# main.net
KiCad netlist of a schematic drawn in EAGLE
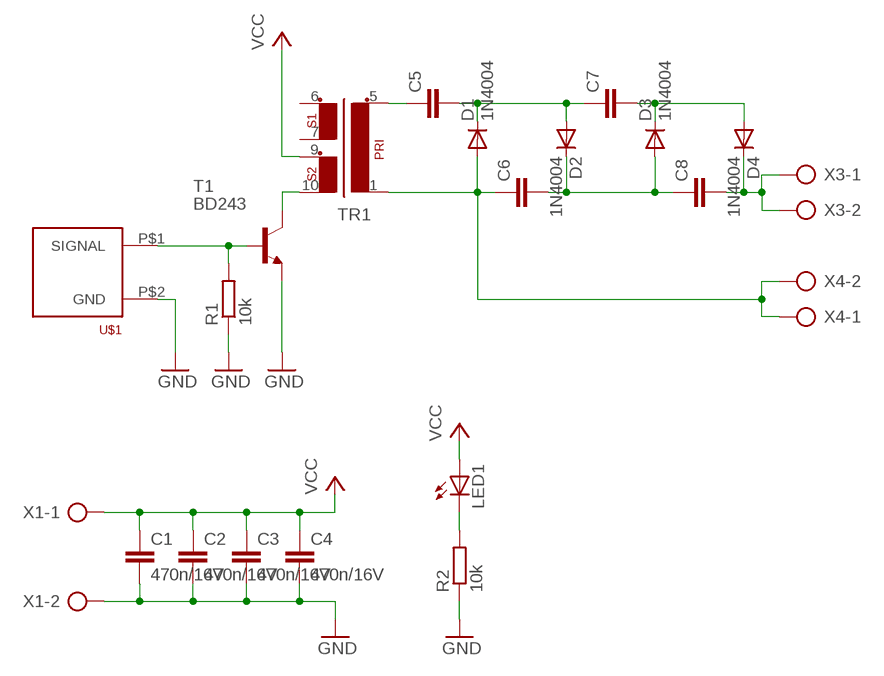
[diagram p0: schematic, sheet 1]

(export (version "E")
  (design (tool "Eeschema 10.0.6"))
  (components
    (comp (ref "C1")
      (value "470n/16V")
      (footprint "eagle-import:C025-025X050")
      (libsource (lib "eagle-import") (part "C-EU025-025X050"))
    )
    (comp (ref "C2")
      (value "470n/16V")
      (footprint "eagle-import:C025-025X050")
      (libsource (lib "eagle-import") (part "C-EU025-025X050"))
    )
    (comp (ref "C3")
      (value "470n/16V")
      (footprint "eagle-import:C025-025X050")
      (libsource (lib "eagle-import") (part "C-EU025-025X050"))
    )
    (comp (ref "C4")
      (value "470n/16V")
      (footprint "eagle-import:C025-025X050")
      (libsource (lib "eagle-import") (part "C-EU025-025X050"))
    )
    (comp (ref "C5")
      (value "C-EU150-064X183")
      (footprint "eagle-import:C150-064X183")
      (libsource (lib "eagle-import") (part "C-EU150-064X183"))
    )
    (comp (ref "C6")
      (value "C-EU150-064X183")
      (footprint "eagle-import:C150-064X183")
      (libsource (lib "eagle-import") (part "C-EU150-064X183"))
    )
    (comp (ref "C7")
      (value "C-EU150-064X183")
      (footprint "eagle-import:C150-064X183")
      (libsource (lib "eagle-import") (part "C-EU150-064X183"))
    )
    (comp (ref "C8")
      (value "C-EU150-064X183")
      (footprint "eagle-import:C150-064X183")
      (libsource (lib "eagle-import") (part "C-EU150-064X183"))
    )
    (comp (ref "D1")
      (value "1N4004")
      (footprint "eagle-import:DO41-10")
      (libsource (lib "eagle-import") (part "1N4004"))
    )
    (comp (ref "D2")
      (value "1N4004")
      (footprint "eagle-import:DO41-10")
      (libsource (lib "eagle-import") (part "1N4004"))
    )
    (comp (ref "D3")
      (value "1N4004")
      (footprint "eagle-import:DO41-10")
      (libsource (lib "eagle-import") (part "1N4004"))
    )
    (comp (ref "D4")
      (value "1N4004")
      (footprint "eagle-import:DO41-10")
      (libsource (lib "eagle-import") (part "1N4004"))
    )
    (comp (ref "LED1")
      (value "LED3MM")
      (footprint "eagle-import:LED3MM")
      (libsource (lib "eagle-import") (part "LED3MM"))
    )
    (comp (ref "R1")
      (value "10k")
      (footprint "eagle-import:M1206")
      (libsource (lib "eagle-import") (part "R-EU_M1206"))
    )
    (comp (ref "R2")
      (value "10k")
      (footprint "eagle-import:M1206")
      (libsource (lib "eagle-import") (part "R-EU_M1206"))
    )
    (comp (ref "T1")
      (value "BD243")
      (footprint "eagle-import:TO220")
      (libsource (lib "eagle-import") (part "BD243"))
    )
    (comp (ref "TR1")
      (value "EI30-2")
      (footprint "eagle-import:EI30-2")
      (libsource (lib "eagle-import") (part "EI30-2"))
    )
    (comp (ref "U$1")
      (value "BNC_VERTICAL")
      (footprint "eagle-import:BNC_VERTICAL")
      (libsource (lib "eagle-import") (part "BNC_VERTICAL"))
    )
    (comp (ref "X1")
      (value "AK500/2-H")
      (footprint "eagle-import:AK500_2-H")
      (libsource (lib "eagle-import") (part "AK500/2-H"))
    )
    (comp (ref "X3")
      (value "AK500/2-H")
      (footprint "eagle-import:AK500_2-H")
      (libsource (lib "eagle-import") (part "AK500/2-H"))
    )
    (comp (ref "X4")
      (value "AK500/2-H")
      (footprint "eagle-import:AK500_2-H")
      (libsource (lib "eagle-import") (part "AK500/2-H"))
    )
  )
  (nets
    (net (code "1") (name "GND") (class "Default")
      (node (ref "C1") (pin "2") (pinfunction "2_2") (pintype "passive"))
      (node (ref "C2") (pin "2") (pinfunction "2_2") (pintype "passive"))
      (node (ref "C3") (pin "2") (pinfunction "2_2") (pintype "passive"))
      (node (ref "C4") (pin "2") (pinfunction "2_2") (pintype "passive"))
      (node (ref "R1") (pin "1") (pinfunction "1_1") (pintype "passive"))
      (node (ref "R2") (pin "1") (pinfunction "1_1") (pintype "passive"))
      (node (ref "T1") (pin "3") (pinfunction "E_3") (pintype "passive"))
      (node (ref "U$1") (pin "P$2") (pinfunction "GND_P$2") (pintype "bidirectional"))
      (node (ref "X1") (pin "2") (pinfunction "KL_2") (pintype "passive"))
    )
    (net (code "2") (name "Net-(C5-Pad2)") (class "Default")
      (node (ref "C5") (pin "2") (pinfunction "2_2") (pintype "passive"))
      (node (ref "C7") (pin "1") (pinfunction "1_1") (pintype "passive"))
      (node (ref "D1") (pin "C") (pinfunction "C_C") (pintype "passive"))
      (node (ref "D2") (pin "A") (pinfunction "A_A") (pintype "passive"))
    )
    (net (code "3") (name "Net-(C6-Pad2)") (class "Default")
      (node (ref "C6") (pin "2") (pinfunction "2_2") (pintype "passive"))
      (node (ref "C8") (pin "1") (pinfunction "1_1") (pintype "passive"))
      (node (ref "D2") (pin "C") (pinfunction "C_C") (pintype "passive"))
      (node (ref "D3") (pin "A") (pinfunction "A_A") (pintype "passive"))
    )
    (net (code "4") (name "Net-(C7-Pad2)") (class "Default")
      (node (ref "C7") (pin "2") (pinfunction "2_2") (pintype "passive"))
      (node (ref "D3") (pin "C") (pinfunction "C_C") (pintype "passive"))
      (node (ref "D4") (pin "A") (pinfunction "A_A") (pintype "passive"))
    )
    (net (code "5") (name "Net-(LED1-C)") (class "Default")
      (node (ref "LED1") (pin "K") (pinfunction "C_K") (pintype "passive"))
      (node (ref "R2") (pin "2") (pinfunction "2_2") (pintype "passive"))
    )
    (net (code "6") (name "Net-(T1-B)") (class "Default")
      (node (ref "R1") (pin "2") (pinfunction "2_2") (pintype "passive"))
      (node (ref "T1") (pin "1") (pinfunction "B_1") (pintype "passive"))
      (node (ref "U$1") (pin "P$1") (pinfunction "SIGNAL_P$1") (pintype "bidirectional"))
    )
    (net (code "7") (name "Net-(T1-C)") (class "Default")
      (node (ref "T1") (pin "2") (pinfunction "C_2") (pintype "passive"))
      (node (ref "TR1") (pin "10") (pinfunction "6_10") (pintype "passive"))
    )
    (net (code "8") (name "Net-(TR1-2)") (class "Default")
      (node (ref "C5") (pin "1") (pinfunction "1_1") (pintype "passive"))
      (node (ref "TR1") (pin "5") (pinfunction "2_5") (pintype "passive"))
    )
    (net (code "9") (name "Net-(X3A-KL)") (class "Default")
      (node (ref "C8") (pin "2") (pinfunction "2_2") (pintype "passive"))
      (node (ref "D4") (pin "C") (pinfunction "C_C") (pintype "passive"))
      (node (ref "X3") (pin "1") (pinfunction "KL_1") (pintype "passive"))
      (node (ref "X3") (pin "2") (pinfunction "KL_2") (pintype "passive"))
    )
    (net (code "10") (name "Net-(X4A-KL)") (class "Default")
      (node (ref "C6") (pin "1") (pinfunction "1_1") (pintype "passive"))
      (node (ref "D1") (pin "A") (pinfunction "A_A") (pintype "passive"))
      (node (ref "TR1") (pin "1") (pinfunction "1_1") (pintype "passive"))
      (node (ref "X4") (pin "1") (pinfunction "KL_1") (pintype "passive"))
      (node (ref "X4") (pin "2") (pinfunction "KL_2") (pintype "passive"))
    )
    (net (code "11") (name "VCC") (class "Default")
      (node (ref "C1") (pin "1") (pinfunction "1_1") (pintype "passive"))
      (node (ref "C2") (pin "1") (pinfunction "1_1") (pintype "passive"))
      (node (ref "C3") (pin "1") (pinfunction "1_1") (pintype "passive"))
      (node (ref "C4") (pin "1") (pinfunction "1_1") (pintype "passive"))
      (node (ref "LED1") (pin "A") (pinfunction "A_A") (pintype "passive"))
      (node (ref "TR1") (pin "9") (pinfunction "5_9") (pintype "passive"))
      (node (ref "X1") (pin "1") (pinfunction "KL_1") (pintype "passive"))
    )
    (net (code "12") (name "unconnected-(TR1-3-Pad6)") (class "Default")
      (node (ref "TR1") (pin "6") (pinfunction "3_6") (pintype "passive"))
    )
    (net (code "13") (name "unconnected-(TR1-4-Pad7)") (class "Default")
      (node (ref "TR1") (pin "7") (pinfunction "4_7") (pintype "passive"))
    )
  )
)
